# SAMV71_Xplained_Ultra_Power_Supply.net
KiCad netlist of a schematic drawn in Altium Designer
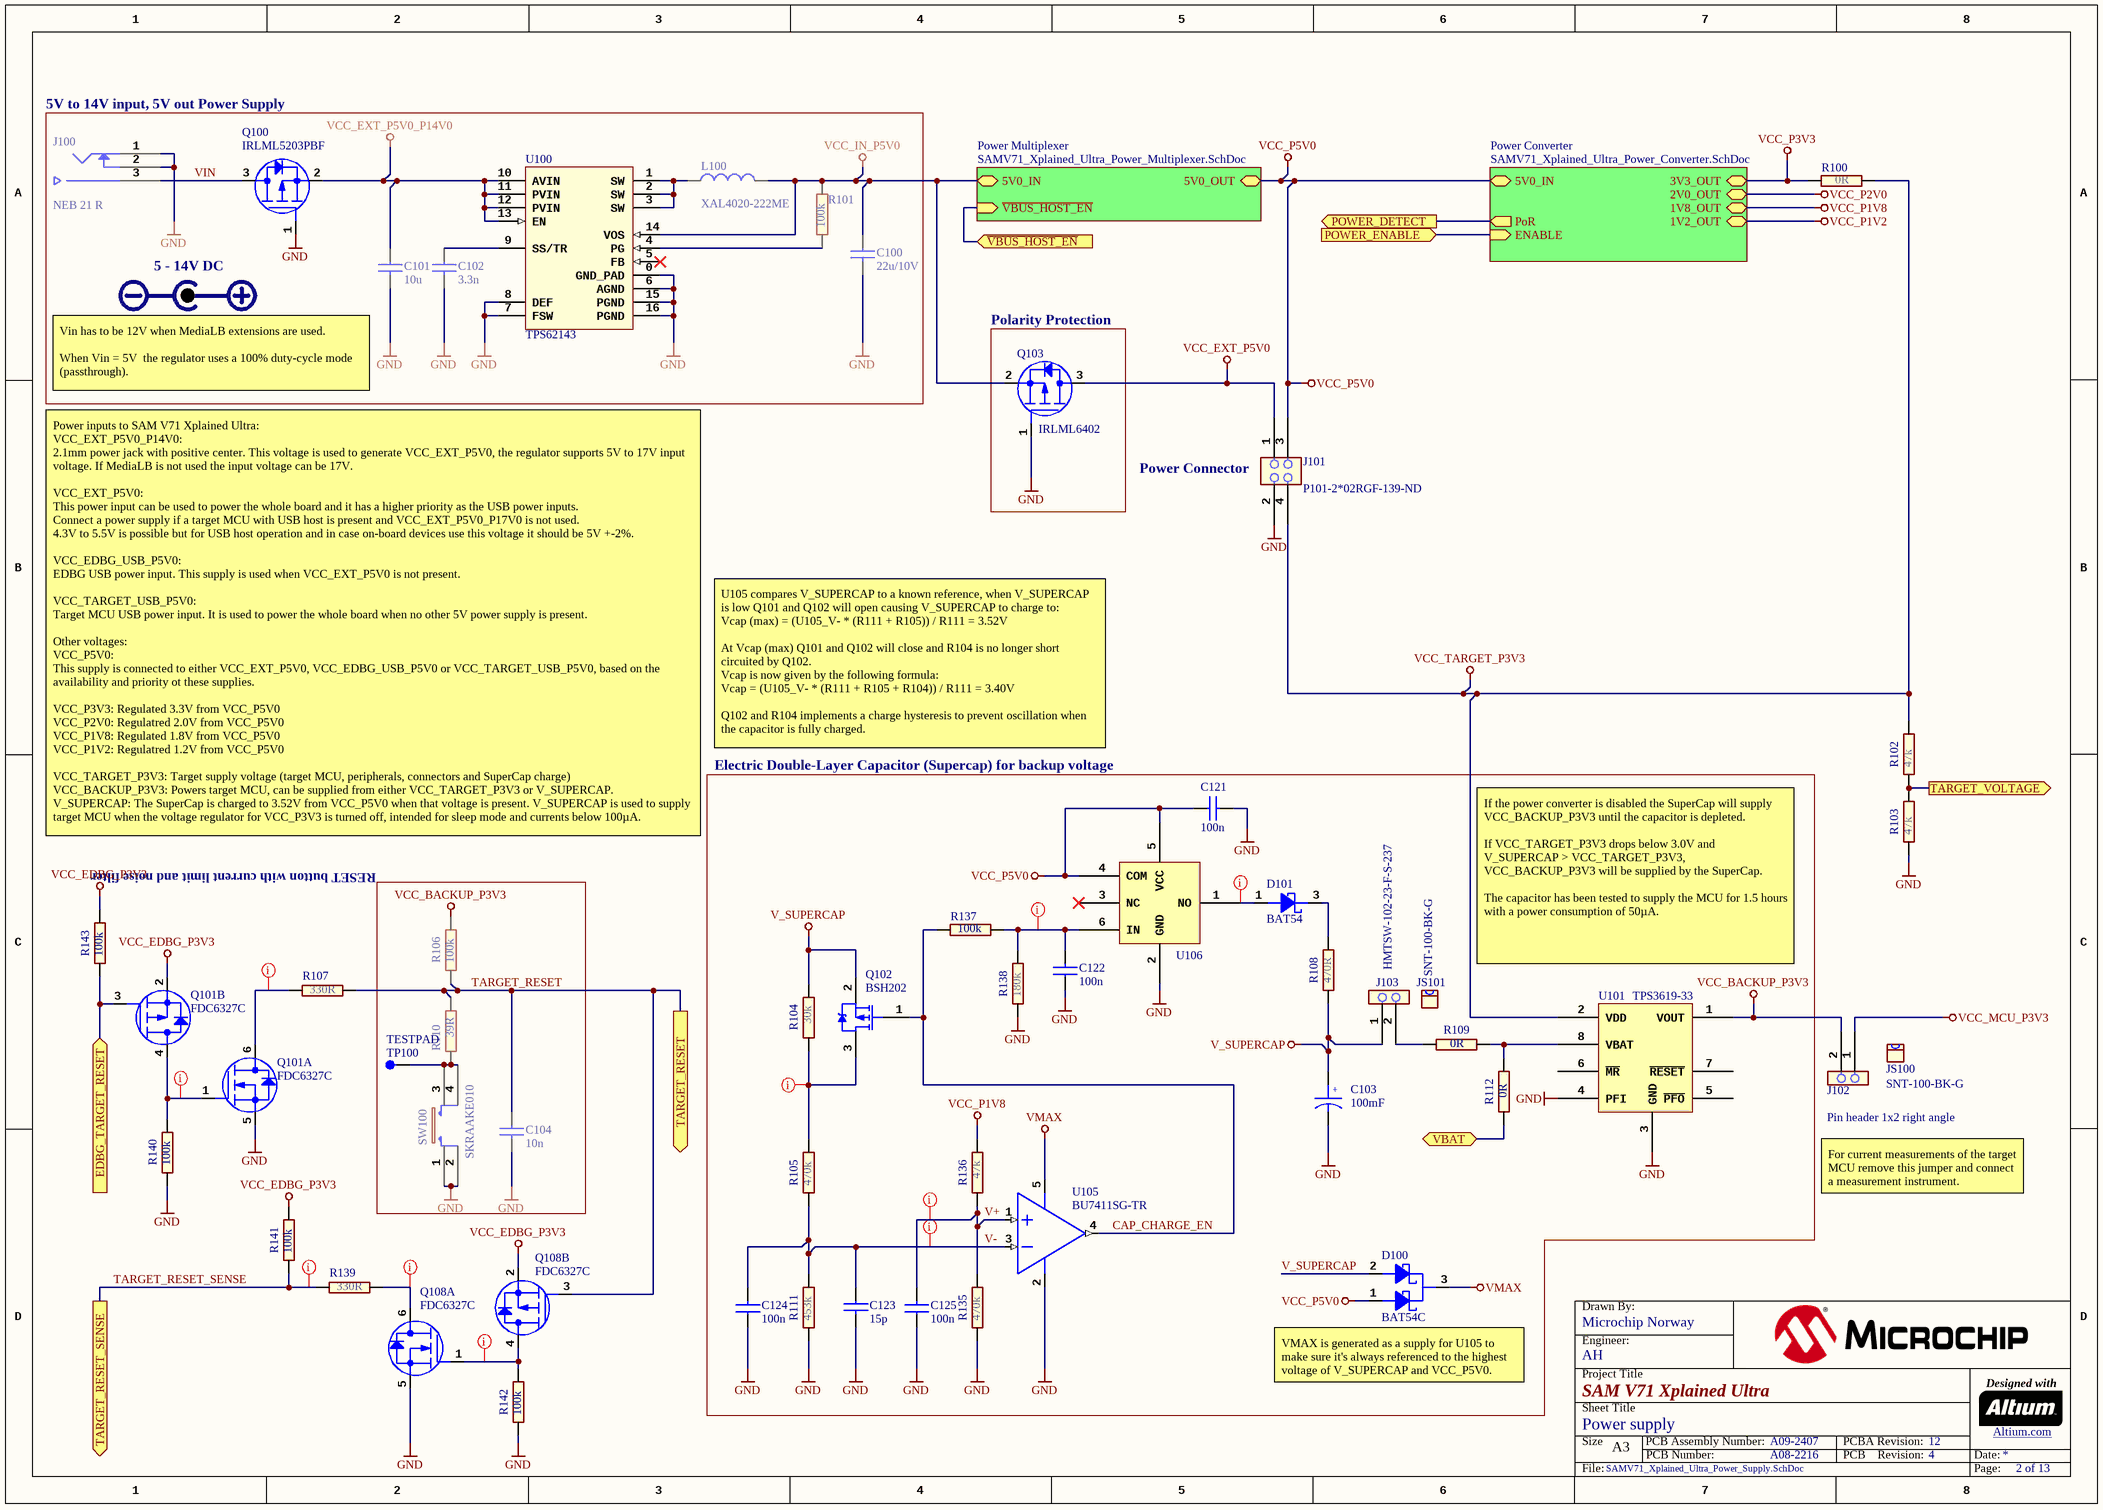
[diagram p0: SAMV71_Xplained_Ultra_Power_Supply.SchDoc]

(export (version "E")
  (design (tool "Eeschema 10.0.6"))
  (components
    (comp (ref "C100")
      (value "22u/10V")
      (footprint "AP1-00003")
      (description "Ceramic capacitor, SMD 0805, X5R, 10V, Â±20%")
      (fields (field (name "MANUFACTURER") "tdk") (field (name "MPN") "C2012X5R1A226M/0.85"))
      (libsource (lib "AltiumDbLib") (part "CAP-NONPOL"))
    )
    (comp (ref "C101")
      (value "10u")
      (footprint "AP1-00003")
      (description "Ceramic capacitor, SMD 0805, X5R, 25V, Â±10%")
      (fields (field (name "TOLERANCE") "Â±10%") (field (name "MANUFACTURER") "Murata"))
      (libsource (lib "AltiumDbLib") (part "CAP-NONPOL"))
    )
    (comp (ref "C102")
      (value "3.3n")
      (footprint "AP1-00001")
      (description "Ceramic capacitor, SMD 0402, X7R, 25V, +/-10%")
      (fields (field (name "TOLERANCE") "25V, +/-10%") (field (name "MANUFACTURER") "YAGEO CORP"))
      (libsource (lib "AltiumDbLib") (part "CAP-NONPOL"))
    )
    (comp (ref "C103")
      (value "100mF")
      (footprint "AP1-00122")
      (description "Electric Double-Layer (Supercapacitor), 100mF, SMD, 10.5mm diameter, 25Î© ESR")
      (fields (field (name "TOLERANCE") "-20/+80%") (field (name "MANUFACTURER") "Kemet"))
      (libsource (lib "AltiumDbLib") (part "CAP-POL"))
    )
    (comp (ref "C104")
      (value "10n")
      (footprint "AP1-00053")
      (description "Ceramic capacitor, SMD 0402, X7R, 25V, +/-10%")
      (fields (field (name "TOLERANCE") "25V, +/-10%") (field (name "MANUFACTURER") "YAGEO CORP"))
      (libsource (lib "AltiumDbLib") (part "CAP-NONPOL"))
    )
    (comp (ref "C121")
      (value "100n")
      (footprint "AP1-00001")
      (description "Ceramic capacitor, SMD 0402, X7R, 16V, +/-10%")
      (fields (field (name "TOLERANCE") "16V, +/-10%") (field (name "MANUFACTURER") "Kemet"))
      (libsource (lib "AltiumDbLib") (part "CAP-NONPOL"))
    )
    (comp (ref "C122")
      (value "100n")
      (footprint "AP1-00053")
      (description "Ceramic capacitor, SMD 0402, X7R, 16V, +/-10%")
      (fields (field (name "TOLERANCE") "16V, +/-10%") (field (name "MANUFACTURER") "Kemet"))
      (libsource (lib "AltiumDbLib") (part "CAP-NONPOL"))
    )
    (comp (ref "C123")
      (value "15p")
      (footprint "AP1-00001")
      (description "Ceramic capacitor, SMD 0402, NP0, 50V, +/-5%")
      (fields (field (name "TOLERANCE") "50V, +/-5%") (field (name "MANUFACTURER") "AVX"))
      (libsource (lib "AltiumDbLib") (part "CAP-NONPOL"))
    )
    (comp (ref "C124")
      (value "100n")
      (footprint "AP1-00001")
      (description "Ceramic capacitor, SMD 0402, X7R, 16V, +/-10%")
      (fields (field (name "TOLERANCE") "16V, +/-10%") (field (name "MANUFACTURER") "Kemet"))
      (libsource (lib "AltiumDbLib") (part "CAP-NONPOL"))
    )
    (comp (ref "C125")
      (value "100n")
      (footprint "AP1-00001")
      (description "Ceramic capacitor, SMD 0402, X7R, 16V, +/-10%")
      (fields (field (name "TOLERANCE") "16V, +/-10%") (field (name "MANUFACTURER") "Kemet"))
      (libsource (lib "AltiumDbLib") (part "CAP-NONPOL"))
    )
    (comp (ref "D100")
      (value "BAT54C")
      (footprint "AP5-00002")
      (description "Schottky double Diodes, NXP, SOT23-3")
      (fields (field (name "MANUFACTURER") "NXP"))
      (libsource (lib "AltiumDbLib") (part "DUAL_SCHOTTKY_123"))
    )
    (comp (ref "D101")
      (value "BAT54")
      (footprint "AP4-00007")
      (fields (field (name "MANUFACTURER") "Philips"))
      (libsource (lib "AltiumDbLib") (part "SCHOTTKY_SMD_31"))
    )
    (comp (ref "J100")
      (value "NEB 21 R")
      (footprint "AP8-00853")
      (description "Through hole DC jack 2.1mm, 12V, 3A")
      (fields (field (name "MANUFACTURER") "Lumberg"))
      (libsource (lib "AltiumDbLib") (part "DC_JACK"))
    )
    (comp (ref "J101")
      (value "P101-2*02RGF-139-ND")
      (footprint "AP8-00628")
      (description "Pin header, 2x2, Right Angle, 2.54mm, THT, Pin In Paste")
      (fields (field (name "MANUFACTURER") "Pro-data International Corp"))
      (libsource (lib "AltiumDbLib") (part "HEADER 2x2"))
    )
    (comp (ref "J102")
      (value "Pin header 1x2 right angle")
      (footprint "AP8-00367")
      (description "1x2 pin header, right angle, 2.54 mm pitch, through-hole")
      (fields (field (name "MANUFACTURER") "Pro-data International Corp") (field (name "MPN") "2213R-2G"))
      (libsource (lib "AltiumDbLib") (part "HEADER 1x2"))
    )
    (comp (ref "J103")
      (value "HMTSW-102-23-F-S-237")
      (footprint "AP8-00733")
      (description "1x2 pin header, 2.54mm pitch, Pin-in-Paste THM")
      (fields (field (name "MANUFACTURER") "SAMTEC"))
      (libsource (lib "") (part "HEADER 1x2_1"))
    )
    (comp (ref "JS100")
      (value "SNT-100-BK-G")
      (footprint "AP8-00525")
      (description "Jumper cap for 2.54mm pinheader")
      (fields (field (name "MANUFACTURER") "SAMTEC"))
      (libsource (lib "AltiumDbLib") (part "JUMPER_CAP"))
    )
    (comp (ref "JS101")
      (value "SNT-100-BK-G")
      (footprint "AP8-00525")
      (description "Jumper cap for 2.54mm pinheader")
      (fields (field (name "MANUFACTURER") "SAMTEC"))
      (libsource (lib "AltiumDbLib") (part "JUMPER_CAP"))
    )
    (comp (ref "L100")
      (value "XAL4020-222ME")
      (footprint "AP3-00119")
      (description "2.2ÂµH Shielded Power Inductor, 4x4x2mm, Isat=5.6A , Irms=4.0A , DCR=35.2mÎ©")
      (fields (field (name "TOLERANCE") "20%") (field (name "MANUFACTURER") "Coilcraft"))
      (libsource (lib "AltiumDbLib") (part "INDUCTOR"))
    )
    (comp (ref "Q100")
      (value "IRLML5203PBF")
      (footprint "AP5-00002")
      (fields (field (name "MANUFACTURER") "International Rectifier"))
      (libsource (lib "AltiumDbLib") (part "MOSFET_P_GSD"))
    )
    (comp (ref "Q101")
      (value "FDC6327C")
      (footprint "AP5-00008")
      (fields (field (name "MANUFACTURER") "Fairchild") (field (name "Comment") "Farnell no: 9844856"))
      (libsource (lib "AltiumDbLib") (part "DUAL_NP_G1S2G2D2S1D1"))
    )
    (comp (ref "Q102")
      (value "BSH202")
      (footprint "AP4-00018")
      (description "P-channel Power MOSFET,30V, 520mA continuous drain current")
      (fields (field (name "MANUFACTURER") "NXP"))
      (libsource (lib "AltiumDbLib") (part "BSH202"))
    )
    (comp (ref "Q103")
      (value "IRLML6402")
      (footprint "AP5-00002")
      (description "P-ch. MOSFET. -30V, -3.7A continuous,RDS(ON)=0.05Ohm@VGS=-4,5V, RDS(ON)=0.08Ohm@VGS=-2.5V")
      (fields (field (name "MANUFACTURER") "International Rectifier") (field (name "MPN") "IRLML6402PBF"))
      (libsource (lib "AltiumDbLib") (part "MOSFET_P_GSD"))
    )
    (comp (ref "Q108")
      (value "FDC6327C")
      (footprint "AP5-00008")
      (fields (field (name "MANUFACTURER") "Fairchild") (field (name "Comment") "Farnell no: 9844856"))
      (libsource (lib "AltiumDbLib") (part "DUAL_NP_G1S2G2D2S1D1"))
    )
    (comp (ref "R100")
      (value "0R")
      (footprint "AP2-00000")
      (description "Thick film resistor, SMD 0402, 1/16W, 1%")
      (fields (field (name "TOLERANCE") "1 %") (field (name "MANUFACTURER") "(n/a)"))
      (libsource (lib "") (part "R2_1"))
    )
    (comp (ref "R101")
      (value "100k")
      (footprint "AP2-00000")
      (description "Thick film resistor, SMD 0402, 1/16W, 1%")
      (fields (field (name "TOLERANCE") "1 %") (field (name "MANUFACTURER") "ASJ"))
      (libsource (lib "") (part "R2_2"))
    )
    (comp (ref "R102")
      (value "47k")
      (footprint "AP2-00000")
      (description "Thick film resistor, SMD 0402, 1/16W, 1%")
      (fields (field (name "TOLERANCE") "1 %") (field (name "MANUFACTURER") "KOA"))
      (libsource (lib "") (part "R2_4"))
    )
    (comp (ref "R103")
      (value "47k")
      (footprint "AP2-00000")
      (description "Thick film resistor, SMD 0402, 1/16W, 1%")
      (fields (field (name "TOLERANCE") "1 %") (field (name "MANUFACTURER") "KOA"))
      (libsource (lib "") (part "R2_4"))
    )
    (comp (ref "R104")
      (value "30k")
      (footprint "AP2-00000")
      (description "Thick film resistor, SMD 0402, 1/16W, 1%")
      (fields (field (name "TOLERANCE") "1 %") (field (name "MANUFACTURER") "ASJ"))
      (libsource (lib "AltiumDbLib") (part "R2"))
    )
    (comp (ref "R105")
      (value "470k")
      (footprint "AP2-00000")
      (description "Thick film resistor, SMD 0402, 1/16W, 1%")
      (fields (field (name "TOLERANCE") "1 %") (field (name "MANUFACTURER") "ASJ"))
      (libsource (lib "AltiumDbLib") (part "R2"))
    )
    (comp (ref "R106")
      (value "100k")
      (footprint "AP2-00011")
      (description "Thick film resistor, SMD 0402, 1/16W, 1%")
      (fields (field (name "TOLERANCE") "1 %") (field (name "MANUFACTURER") "ASJ"))
      (libsource (lib "AltiumDbLib") (part "R2"))
    )
    (comp (ref "R107")
      (value "330R")
      (footprint "AP2-00011")
      (description "Thick film resistor, SMD 0402, 1/16W, 1%")
      (fields (field (name "TOLERANCE") "1 %") (field (name "MANUFACTURER") "ASJ"))
      (libsource (lib "") (part "R2_1"))
    )
    (comp (ref "R108")
      (value "470R")
      (footprint "AP2-00000")
      (description "Thick film resistor, SMD 0402, 1/16W, 1%")
      (fields (field (name "TOLERANCE") "1 %") (field (name "MANUFACTURER") "ASJ"))
      (libsource (lib "") (part "R2_2"))
    )
    (comp (ref "R109")
      (value "0R")
      (footprint "AP2-00000")
      (description "RES 0.0 OHM 1/16W 0402 SMD")
      (fields (field (name "TOLERANCE") "1 %") (field (name "MANUFACTURER") "(n/a)"))
      (libsource (lib "") (part "R2_1"))
    )
    (comp (ref "R110")
      (value "39R")
      (footprint "AP2-00011")
      (description "Thick film resistor, SMD 0402, 1/16W, 1%")
      (fields (field (name "TOLERANCE") "1 %") (field (name "MANUFACTURER") "ASJ"))
      (libsource (lib "") (part "R2_3"))
    )
    (comp (ref "R111")
      (value "453k")
      (footprint "AP2-00000")
      (description "Thick film resistor, SMD 0402, 1/16W, 1%")
      (fields (field (name "TOLERANCE") "1 %"))
      (libsource (lib "AltiumDbLib") (part "R2"))
    )
    (comp (ref "R112")
      (value "0R")
      (footprint "AP2-00000")
      (description "RES 0.0 OHM 1/16W 0402 SMD")
      (fields (field (name "TOLERANCE") "1 %") (field (name "MANUFACTURER") "(n/a)"))
      (libsource (lib "AltiumDbLib") (part "R2"))
    )
    (comp (ref "R135")
      (value "470k")
      (footprint "AP2-00000")
      (description "Thick film resistor, SMD 0402, 1/16W, 1%")
      (fields (field (name "TOLERANCE") "1 %") (field (name "MANUFACTURER") "ASJ"))
      (libsource (lib "AltiumDbLib") (part "R2"))
    )
    (comp (ref "R136")
      (value "47k")
      (footprint "AP2-00000")
      (description "Thick film resistor, SMD 0402, 1/16W, 1%")
      (fields (field (name "TOLERANCE") "1 %") (field (name "MANUFACTURER") "KOA"))
      (libsource (lib "AltiumDbLib") (part "R2"))
    )
    (comp (ref "R137")
      (value "100k")
      (footprint "AP2-00011")
      (description "Thick film resistor, SMD 0402, 1/16W, 1%")
      (fields (field (name "TOLERANCE") "1 %") (field (name "MANUFACTURER") "ASJ"))
      (libsource (lib "") (part "R2_1"))
    )
    (comp (ref "R138")
      (value "180k")
      (footprint "AP2-00011")
      (description "Thick film resistor, SMD 0402, 1/16W, 1%")
      (fields (field (name "TOLERANCE") "1 %") (field (name "MANUFACTURER") "ASJ"))
      (libsource (lib "AltiumDbLib") (part "R2"))
    )
    (comp (ref "R139")
      (value "330R")
      (footprint "AP2-00011")
      (description "Thick film resistor, SMD 0402, 1/16W, 1%")
      (fields (field (name "TOLERANCE") "1 %") (field (name "MANUFACTURER") "ASJ"))
      (libsource (lib "") (part "R2_1"))
    )
    (comp (ref "R140")
      (value "100k")
      (footprint "AP2-00011")
      (description "Thick film resistor, SMD 0402, 1/16W, 1%")
      (fields (field (name "TOLERANCE") "1 %") (field (name "MANUFACTURER") "ASJ"))
      (libsource (lib "AltiumDbLib") (part "R2"))
    )
    (comp (ref "R141")
      (value "100k")
      (footprint "AP2-00011")
      (description "Thick film resistor, SMD 0402, 1/16W, 1%")
      (fields (field (name "TOLERANCE") "1 %") (field (name "MANUFACTURER") "ASJ"))
      (libsource (lib "AltiumDbLib") (part "R2"))
    )
    (comp (ref "R142")
      (value "100k")
      (footprint "AP2-00011")
      (description "Thick film resistor, SMD 0402, 1/16W, 1%")
      (fields (field (name "TOLERANCE") "1 %") (field (name "MANUFACTURER") "ASJ"))
      (libsource (lib "AltiumDbLib") (part "R2"))
    )
    (comp (ref "R143")
      (value "100k")
      (footprint "AP2-00011")
      (description "Thick film resistor, SMD 0402, 1/16W, 1%")
      (fields (field (name "TOLERANCE") "1 %") (field (name "MANUFACTURER") "ASJ"))
      (libsource (lib "AltiumDbLib") (part "R2"))
    )
    (comp (ref "SW100")
      (value "SKRAAKE010")
      (footprint "AP8-00137")
      (description "6.2x6.2 mm SMD tact switch, same as A08-0091 but less force is needed")
      (fields (field (name "MANUFACTURER") "ALPS"))
      (libsource (lib "AltiumDbLib") (part "PUSHBUTTON1"))
    )
    (comp (ref "TP100")
      (value "TESTPAD")
      (footprint "AP8-00010")
      (description "Single SMD testpad")
      (libsource (lib "AltiumDbLib") (part "TESTPOINT"))
    )
    (comp (ref "U100")
      (value "TPS62143")
      (footprint "AP6-00313")
      (description "5V to 17V in, 5V 2A out, Step-Down Converter")
      (fields (field (name "MANUFACTURER") "Texas Instruments") (field (name "MPN") "TPS62143RGTR"))
      (libsource (lib "AltiumDbLib") (part "TPS62143"))
    )
    (comp (ref "U101")
      (value "TPS3619-33")
      (footprint "AP6-00382")
      (description "Backup battery supervisors for RAM retention")
      (fields (field (name "MANUFACTURER") "Texas Instruments") (field (name "MPN") "TPS3619-33DGK"))
      (libsource (lib "AltiumDbLib") (part "TPS3619"))
    )
    (comp (ref "U105")
      (value "BU7411SG-TR")
      (footprint "AP6-00087")
      (description "Single, Low Voltage (1.6-5.5V), Low Power (0.35ÂµA), low cost")
      (fields (field (name "MANUFACTURER") "ROHM"))
      (libsource (lib "AltiumDbLib") (part "LMV321M5"))
    )
    (comp (ref "U106")
      (value "~")
      (footprint "AP6-00056")
      (description "1.65V to 5.5V SPDT Analog switch")
      (fields (field (name "MANUFACTURER") "Texas Instruments") (field (name "MPN") "TS5A3160DBVR"))
      (libsource (lib "AltiumDbLib") (part "TS5A3160"))
    )
  )
  (nets
    (net (code "1") (name "/CAP_CHARGE_EN") (class "Default")
      (node (ref "Q102") (pin "1") (pinfunction "G_1") (pintype "passive"))
      (node (ref "R137") (pin "1") (pinfunction "1_1") (pintype "passive"))
      (node (ref "U105") (pin "4") (pinfunction "OUT_4") (pintype "output"))
    )
    (net (code "2") (name "/EDBG_TARGET_RESET") (class "Default")
      (node (ref "Q101") (pin "3") (pinfunction "G_3") (pintype "passive"))
      (node (ref "R143") (pin "1") (pinfunction "1_1") (pintype "passive"))
    )
    (net (code "5") (name "/TARGET_RESET") (class "Default")
      (node (ref "C104") (pin "1") (pinfunction "1_1") (pintype "passive"))
      (node (ref "Q108") (pin "3") (pinfunction "G_3") (pintype "passive"))
      (node (ref "R106") (pin "1") (pinfunction "1_1") (pintype "passive"))
      (node (ref "R107") (pin "2") (pinfunction "2_2") (pintype "passive"))
      (node (ref "R110") (pin "2") (pinfunction "2_2") (pintype "passive"))
    )
    (net (code "6") (name "/TARGET_RESET_SENSE") (class "Default")
      (node (ref "R139") (pin "1") (pinfunction "1_1") (pintype "passive"))
      (node (ref "R141") (pin "1") (pinfunction "1_1") (pintype "passive"))
    )
    (net (code "7") (name "/TARGET_VOLTAGE") (class "Default")
      (node (ref "R102") (pin "1") (pinfunction "1_1") (pintype "passive"))
      (node (ref "R103") (pin "2") (pinfunction "2_2") (pintype "passive"))
    )
    (net (code "8") (name "/V+") (class "Default")
      (node (ref "C125") (pin "2") (pinfunction "2_2") (pintype "passive"))
      (node (ref "R135") (pin "2") (pinfunction "2_2") (pintype "passive"))
      (node (ref "R136") (pin "1") (pinfunction "1_1") (pintype "passive"))
      (node (ref "U105") (pin "1") (pinfunction "IN+_1") (pintype "input"))
    )
    (net (code "9") (name "/V-") (class "Default")
      (node (ref "C123") (pin "1") (pinfunction "1_1") (pintype "passive"))
      (node (ref "C124") (pin "2") (pinfunction "2_2") (pintype "passive"))
      (node (ref "R105") (pin "1") (pinfunction "1_1") (pintype "passive"))
      (node (ref "R111") (pin "2") (pinfunction "2_2") (pintype "passive"))
      (node (ref "U105") (pin "3") (pinfunction "IN-_3") (pintype "input"))
    )
    (net (code "10") (name "/VBAT") (class "Default")
      (node (ref "R112") (pin "1") (pinfunction "1_1") (pintype "passive"))
    )
    (net (code "11") (name "/VIN") (class "Default")
      (node (ref "J100") (pin "3") (pinfunction "3_3") (pintype "passive"))
      (node (ref "Q100") (pin "3") (pinfunction "D_3") (pintype "passive"))
    )
    (net (code "13") (name "GND") (class "Default")
      (node (ref "C100") (pin "2") (pinfunction "2_2") (pintype "passive"))
      (node (ref "C101") (pin "2") (pinfunction "2_2") (pintype "passive"))
      (node (ref "C102") (pin "2") (pinfunction "2_2") (pintype "passive"))
      (node (ref "C103") (pin "2") (pinfunction "2_2") (pintype "passive"))
      (node (ref "C104") (pin "2") (pinfunction "2_2") (pintype "passive"))
      (node (ref "C121") (pin "2") (pinfunction "2_2") (pintype "passive"))
      (node (ref "C122") (pin "1") (pinfunction "1_1") (pintype "passive"))
      (node (ref "C123") (pin "2") (pinfunction "2_2") (pintype "passive"))
      (node (ref "C124") (pin "1") (pinfunction "1_1") (pintype "passive"))
      (node (ref "C125") (pin "1") (pinfunction "1_1") (pintype "passive"))
      (node (ref "J100") (pin "1") (pinfunction "1_1") (pintype "passive"))
      (node (ref "J100") (pin "2") (pinfunction "2_2") (pintype "passive"))
      (node (ref "J101") (pin "2") (pinfunction "2_2") (pintype "passive"))
      (node (ref "Q100") (pin "1") (pinfunction "G_1") (pintype "passive"))
      (node (ref "Q101") (pin "5") (pinfunction "S_5") (pintype "passive"))
      (node (ref "Q103") (pin "1") (pinfunction "G_1") (pintype "passive"))
      (node (ref "Q108") (pin "5") (pinfunction "S_5") (pintype "passive"))
      (node (ref "R103") (pin "1") (pinfunction "1_1") (pintype "passive"))
      (node (ref "R111") (pin "1") (pinfunction "1_1") (pintype "passive"))
      (node (ref "R135") (pin "1") (pinfunction "1_1") (pintype "passive"))
      (node (ref "R138") (pin "1") (pinfunction "1_1") (pintype "passive"))
      (node (ref "R140") (pin "1") (pinfunction "1_1") (pintype "passive"))
      (node (ref "R142") (pin "1") (pinfunction "1_1") (pintype "passive"))
      (node (ref "SW100") (pin "1") (pinfunction "1_1") (pintype "passive"))
      (node (ref "SW100") (pin "2") (pinfunction "2_2") (pintype "passive"))
      (node (ref "U100") (pin "0") (pinfunction "GND_PAD_0") (pintype "passive"))
      (node (ref "U100") (pin "15") (pinfunction "PGND_15") (pintype "power_in"))
      (node (ref "U100") (pin "16") (pinfunction "PGND_16") (pintype "power_in"))
      (node (ref "U100") (pin "6") (pinfunction "AGND_6") (pintype "power_in"))
      (node (ref "U100") (pin "7") (pinfunction "FSW_7") (pintype "power_in"))
      (node (ref "U100") (pin "8") (pinfunction "DEF_8") (pintype "power_in"))
      (node (ref "U101") (pin "3") (pinfunction "GND_3") (pintype "passive"))
      (node (ref "U101") (pin "4") (pinfunction "PFI_4") (pintype "passive"))
      (node (ref "U105") (pin "2") (pinfunction "GND_2") (pintype "power_in"))
      (node (ref "U106") (pin "2") (pinfunction "GND_2") (pintype "passive"))
    )
    (net (code "14") (name "Net-(D101-ANODE)") (class "Default")
      (node (ref "D101") (pin "1") (pinfunction "ANODE_1") (pintype "passive"))
      (node (ref "U106") (pin "1") (pinfunction "NO_1") (pintype "passive"))
    )
    (net (code "15") (name "Net-(D101-CATHODE)") (class "Default")
      (node (ref "D101") (pin "3") (pinfunction "CATHODE_3") (pintype "passive"))
      (node (ref "R108") (pin "1") (pinfunction "1_1") (pintype "passive"))
    )
    (net (code "16") (name "Net-(J103-Pad2)") (class "Default")
      (node (ref "J103") (pin "2") (pinfunction "2_2") (pintype "passive"))
      (node (ref "R109") (pin "1") (pinfunction "1_1") (pintype "passive"))
    )
    (net (code "17") (name "Net-(L100-Pad1)") (class "Default")
      (node (ref "L100") (pin "1") (pinfunction "1_1") (pintype "passive"))
      (node (ref "U100") (pin "1") (pinfunction "SW_1") (pintype "power_in"))
      (node (ref "U100") (pin "2") (pinfunction "SW_2") (pintype "power_in"))
      (node (ref "U100") (pin "3") (pinfunction "SW_3") (pintype "power_in"))
    )
    (net (code "18") (name "Net-(Q101A-D)") (class "Default")
      (node (ref "Q101") (pin "6") (pinfunction "D_6") (pintype "passive"))
      (node (ref "R107") (pin "1") (pinfunction "1_1") (pintype "passive"))
    )
    (net (code "19") (name "Net-(Q101A-G)") (class "Default")
      (node (ref "Q101") (pin "1") (pinfunction "G_1") (pintype "passive"))
      (node (ref "Q101") (pin "4") (pinfunction "D_4") (pintype "passive"))
      (node (ref "R140") (pin "2") (pinfunction "2_2") (pintype "passive"))
    )
    (net (code "20") (name "Net-(Q102-D)") (class "Default")
      (node (ref "Q102") (pin "3") (pinfunction "D_3") (pintype "passive"))
      (node (ref "R104") (pin "1") (pinfunction "1_1") (pintype "passive"))
      (node (ref "R105") (pin "2") (pinfunction "2_2") (pintype "passive"))
    )
    (net (code "21") (name "Net-(Q108A-D)") (class "Default")
      (node (ref "Q108") (pin "6") (pinfunction "D_6") (pintype "passive"))
      (node (ref "R139") (pin "2") (pinfunction "2_2") (pintype "passive"))
    )
    (net (code "22") (name "Net-(Q108A-G)") (class "Default")
      (node (ref "Q108") (pin "1") (pinfunction "G_1") (pintype "passive"))
      (node (ref "Q108") (pin "4") (pinfunction "D_4") (pintype "passive"))
      (node (ref "R142") (pin "2") (pinfunction "2_2") (pintype "passive"))
    )
    (net (code "23") (name "Net-(R110-Pad1)") (class "Default")
      (node (ref "R110") (pin "1") (pinfunction "1_1") (pintype "passive"))
      (node (ref "SW100") (pin "3") (pinfunction "3_3") (pintype "passive"))
      (node (ref "SW100") (pin "4") (pinfunction "4_4") (pintype "passive"))
      (node (ref "TP100") (pin "1") (pinfunction "1_1") (pintype "passive"))
    )
    (net (code "24") (name "Net-(U100-PG)") (class "Default")
      (node (ref "R101") (pin "2") (pinfunction "2_2") (pintype "passive"))
      (node (ref "U100") (pin "4") (pinfunction "PG_4") (pintype "input"))
    )
    (net (code "25") (name "Net-(U100-SS{slash}TR)") (class "Default")
      (node (ref "C102") (pin "1") (pinfunction "1_1") (pintype "passive"))
      (node (ref "U100") (pin "9") (pinfunction "SS/TR_9") (pintype "passive"))
    )
    (net (code "26") (name "Net-(U101-VBAT)") (class "Default")
      (node (ref "R109") (pin "2") (pinfunction "2_2") (pintype "passive"))
      (node (ref "R112") (pin "2") (pinfunction "2_2") (pintype "passive"))
      (node (ref "U101") (pin "8") (pinfunction "VBAT_8") (pintype "passive"))
    )
    (net (code "27") (name "Net-(U106-IN)") (class "Default")
      (node (ref "C122") (pin "2") (pinfunction "2_2") (pintype "passive"))
      (node (ref "R137") (pin "2") (pinfunction "2_2") (pintype "passive"))
      (node (ref "R138") (pin "2") (pinfunction "2_2") (pintype "passive"))
      (node (ref "U106") (pin "6") (pinfunction "IN_6") (pintype "passive"))
    )
    (net (code "28") (name "VCC_BACKUP_P3V3") (class "Default")
      (node (ref "J102") (pin "2") (pinfunction "2_2") (pintype "passive"))
      (node (ref "R106") (pin "2") (pinfunction "2_2") (pintype "passive"))
      (node (ref "U101") (pin "1") (pinfunction "VOUT_1") (pintype "passive"))
    )
    (net (code "29") (name "VCC_EDBG_P3V3") (class "Default")
      (node (ref "Q101") (pin "2") (pinfunction "S_2") (pintype "passive"))
      (node (ref "Q108") (pin "2") (pinfunction "S_2") (pintype "passive"))
      (node (ref "R141") (pin "2") (pinfunction "2_2") (pintype "passive"))
      (node (ref "R143") (pin "2") (pinfunction "2_2") (pintype "passive"))
    )
    (net (code "30") (name "VCC_EXT_P5V0") (class "Default")
      (node (ref "J101") (pin "1") (pinfunction "1_1") (pintype "passive"))
      (node (ref "Q103") (pin "3") (pinfunction "D_3") (pintype "passive"))
    )
    (net (code "31") (name "VCC_EXT_P5V0_P14V0") (class "Default")
      (node (ref "C101") (pin "1") (pinfunction "1_1") (pintype "passive"))
      (node (ref "Q100") (pin "2") (pinfunction "S_2") (pintype "passive"))
      (node (ref "U100") (pin "10") (pinfunction "AVIN_10") (pintype "power_in"))
      (node (ref "U100") (pin "11") (pinfunction "PVIN_11") (pintype "power_in"))
      (node (ref "U100") (pin "12") (pinfunction "PVIN_12") (pintype "power_in"))
      (node (ref "U100") (pin "13") (pinfunction "EN_13") (pintype "input"))
    )
    (net (code "32") (name "VCC_IN_P5V0") (class "Default")
      (node (ref "C100") (pin "1") (pinfunction "1_1") (pintype "passive"))
      (node (ref "L100") (pin "2") (pinfunction "2_2") (pintype "passive"))
      (node (ref "Q103") (pin "2") (pinfunction "S_2") (pintype "passive"))
      (node (ref "R101") (pin "1") (pinfunction "1_1") (pintype "passive"))
      (node (ref "U100") (pin "14") (pinfunction "VOS_14") (pintype "input"))
    )
    (net (code "33") (name "VCC_MCU_P3V3") (class "Default")
      (node (ref "J102") (pin "1") (pinfunction "1_1") (pintype "passive"))
    )
    (net (code "35") (name "VCC_P1V8") (class "Default")
      (node (ref "R136") (pin "2") (pinfunction "2_2") (pintype "passive"))
    )
    (net (code "37") (name "VCC_P3V3") (class "Default")
      (node (ref "R100") (pin "1") (pinfunction "1_1") (pintype "passive"))
    )
    (net (code "38") (name "VCC_P5V0") (class "Default")
      (node (ref "C121") (pin "1") (pinfunction "1_1") (pintype "passive"))
      (node (ref "D100") (pin "1") (pinfunction "ANODE1_1") (pintype "passive"))
      (node (ref "J101") (pin "3") (pinfunction "3_3") (pintype "passive"))
      (node (ref "U106") (pin "4") (pinfunction "COM_4") (pintype "passive"))
      (node (ref "U106") (pin "5") (pinfunction "VCC_5") (pintype "passive"))
    )
    (net (code "39") (name "VCC_TARGET_P3V3") (class "Default")
      (node (ref "J101") (pin "4") (pinfunction "4_4") (pintype "passive"))
      (node (ref "R100") (pin "2") (pinfunction "2_2") (pintype "passive"))
      (node (ref "R102") (pin "2") (pinfunction "2_2") (pintype "passive"))
      (node (ref "U101") (pin "2") (pinfunction "VDD_2") (pintype "passive"))
    )
    (net (code "40") (name "VMAX") (class "Default")
      (node (ref "D100") (pin "3") (pinfunction "CATHODE_3") (pintype "passive"))
      (node (ref "U105") (pin "5") (pinfunction "VCC_5") (pintype "power_in"))
    )
    (net (code "41") (name "V_SUPERCAP") (class "Default")
      (node (ref "C103") (pin "1") (pinfunction "1_1") (pintype "passive"))
      (node (ref "D100") (pin "2") (pinfunction "ANODE2_2") (pintype "passive"))
      (node (ref "J103") (pin "1") (pinfunction "1_1") (pintype "passive"))
      (node (ref "Q102") (pin "2") (pinfunction "S_2") (pintype "passive"))
      (node (ref "R104") (pin "2") (pinfunction "2_2") (pintype "passive"))
      (node (ref "R108") (pin "2") (pinfunction "2_2") (pintype "passive"))
    )
    (net (code "42") (name "unconnected-(U100-FB-Pad5)") (class "Default")
      (node (ref "U100") (pin "5") (pinfunction "FB_5") (pintype "input+no_connect"))
    )
    (net (code "43") (name "unconnected-(U101-~{MR}-Pad6)") (class "Default")
      (node (ref "U101") (pin "6") (pinfunction "~{MR}_6") (pintype "passive"))
    )
    (net (code "44") (name "unconnected-(U101-~{PFO}-Pad5)") (class "Default")
      (node (ref "U101") (pin "5") (pinfunction "~{PFO}_5") (pintype "passive"))
    )
    (net (code "45") (name "unconnected-(U101-~{RESET}-Pad7)") (class "Default")
      (node (ref "U101") (pin "7") (pinfunction "~{RESET}_7") (pintype "passive"))
    )
    (net (code "46") (name "unconnected-(U106-NC-Pad3)") (class "Default")
      (node (ref "U106") (pin "3") (pinfunction "NC_3") (pintype "passive+no_connect"))
    )
  )
)
